# 09_UART_JTAG_GPIO.net
KiCad netlist of a schematic drawn in Altium Designer
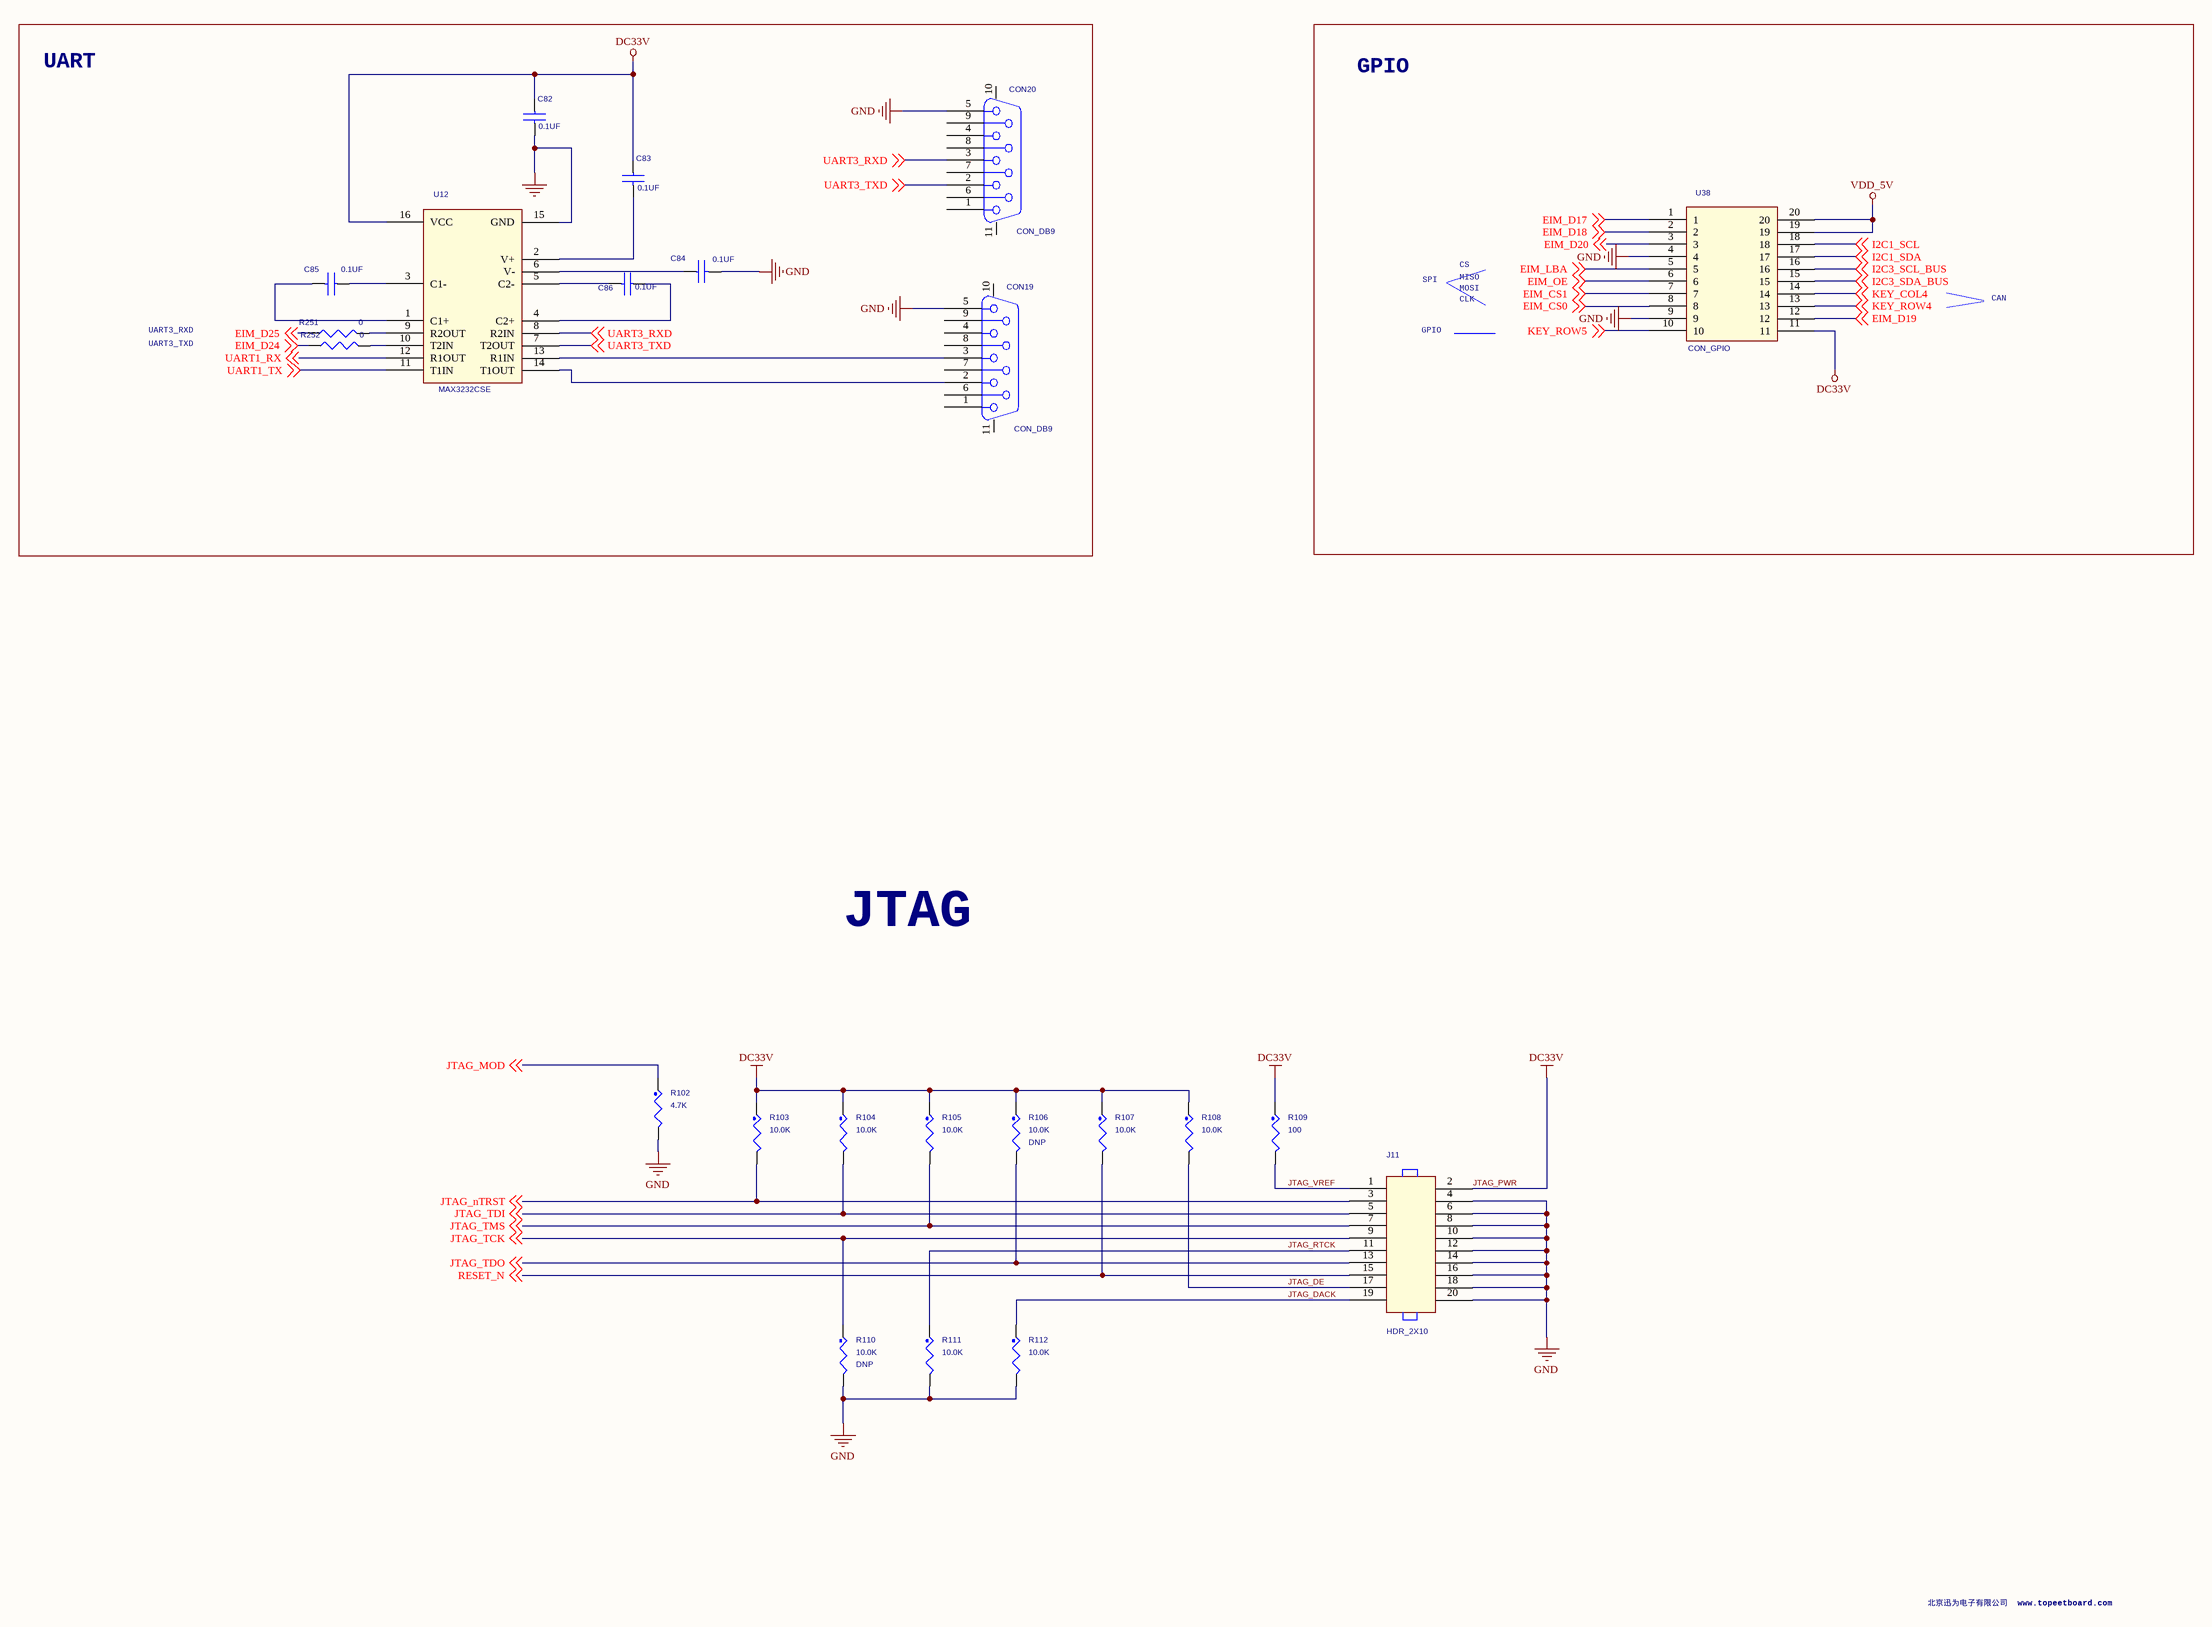
[diagram p0: 09 UART,JTAG,GPIO.SchDoc]

(export (version "E")
  (design (tool "Eeschema 10.0.6"))
  (components
    (comp (ref "C82") (value "0.1UF") (footprint "C0603") (libsource (lib "*") (part "C0603_0_Dup1")))
    (comp (ref "C83") (value "0.1UF") (footprint "C0603") (libsource (lib "*") (part "C0603_0_Dup1")))
    (comp (ref "C84") (value "0.1UF") (footprint "C0603") (libsource (lib "*") (part "C0603_0_Dup1")))
    (comp (ref "C85") (value "0.1UF") (footprint "C0603") (libsource (lib "*") (part "C0603_0_Dup1")))
    (comp (ref "C86") (value "0.1UF") (footprint "C0603") (libsource (lib "*") (part "C0603_0_Dup1")))
    (comp (ref "CON19") (value "CON_DB9") (footprint "DB9") (libsource (lib "*") (part "CON_DB9")))
    (comp (ref "CON20") (value "CON_DB9") (footprint "DB9") (libsource (lib "*") (part "CON_DB9")))
    (comp (ref "J11")
      (value "HDR_2X10")
      (description "HDR 2X10 TH SHRD 100MIL CTR 393H AU 120L")
      (libsource (lib "*") (part "HDR_2X10"))
    )
    (comp (ref "R102")
      (value "4.7K")
      (description "RES MF 4.70K 1/16W 1% 0402")
      (fields (field (name "TOLERANCE") "1%"))
      (libsource (lib "*") (part "RES_Dup1"))
    )
    (comp (ref "R103")
      (value "10.0K")
      (description "RES MF 10.0K 1/16W 1% AEC-Q200 0402")
      (fields (field (name "TOLERANCE") "1%"))
      (libsource (lib "*") (part "RES_Dup1"))
    )
    (comp (ref "R104")
      (value "10.0K")
      (description "RES MF 10.0K 1/16W 1% AEC-Q200 0402")
      (fields (field (name "TOLERANCE") "1%"))
      (libsource (lib "*") (part "RES_Dup1"))
    )
    (comp (ref "R105")
      (value "10.0K")
      (description "RES MF 10.0K 1/16W 1% AEC-Q200 0402")
      (fields (field (name "TOLERANCE") "1%"))
      (libsource (lib "*") (part "RES_Dup1"))
    )
    (comp (ref "R106")
      (value "10.0K")
      (description "RES MF 10.0K 1/16W 1% AEC-Q200 0402")
      (fields (field (name "TOLERANCE") "1%") (field (name "ASSY_OPT") "DNP"))
      (libsource (lib "*") (part "RES_Dup1"))
    )
    (comp (ref "R107")
      (value "10.0K")
      (description "RES MF 10.0K 1/16W 1% AEC-Q200 0402")
      (fields (field (name "TOLERANCE") "1%"))
      (libsource (lib "*") (part "RES_Dup1"))
    )
    (comp (ref "R108")
      (value "10.0K")
      (description "RES MF 10.0K 1/16W 1% AEC-Q200 0402")
      (fields (field (name "TOLERANCE") "1%"))
      (libsource (lib "*") (part "RES_Dup1"))
    )
    (comp (ref "R109")
      (value "100")
      (description "RES MF 100 OHM 1/16W 1% 0402")
      (fields (field (name "TOLERANCE") "1%"))
      (libsource (lib "*") (part "RES_Dup1"))
    )
    (comp (ref "R110")
      (value "10.0K")
      (description "RES MF 10.0K 1/16W 1% AEC-Q200 0402")
      (fields (field (name "TOLERANCE") "1%") (field (name "ASSY_OPT") "DNP"))
      (libsource (lib "*") (part "RES_Dup1"))
    )
    (comp (ref "R111")
      (value "10.0K")
      (description "RES MF 10.0K 1/16W 1% AEC-Q200 0402")
      (fields (field (name "TOLERANCE") "1%"))
      (libsource (lib "*") (part "RES_Dup1"))
    )
    (comp (ref "R112")
      (value "10.0K")
      (description "RES MF 10.0K 1/16W 1% AEC-Q200 0402")
      (fields (field (name "TOLERANCE") "1%"))
      (libsource (lib "*") (part "RES_Dup1"))
    )
    (comp (ref "R251") (value "0") (footprint "R1005") (libsource (lib "*") (part "R1005_0_Dup1")))
    (comp (ref "R252") (value "0") (footprint "R1005") (libsource (lib "*") (part "R1005_0_Dup1")))
    (comp (ref "U12") (value "MAX3232CSE") (footprint "16") (libsource (lib "*") (part "MAX3232EEAE")))
    (comp (ref "U38") (value "CON_GPIO") (libsource (lib "*") (part "CON20_1")))
  )
  (nets
    (net (code "1") (name "/JTAG_DACK") (class "Default")
      (node (ref "J11") (pin "19") (pinfunction "19_19") (pintype "passive"))
      (node (ref "R112") (pin "1") (pinfunction "1_1") (pintype "passive"))
    )
    (net (code "2") (name "/JTAG_DE") (class "Default")
      (node (ref "J11") (pin "17") (pinfunction "17_17") (pintype "passive"))
      (node (ref "R108") (pin "2") (pinfunction "2_2") (pintype "passive"))
    )
    (net (code "3") (name "/JTAG_RTCK") (class "Default")
      (node (ref "J11") (pin "11") (pinfunction "11_11") (pintype "passive"))
      (node (ref "R111") (pin "1") (pinfunction "1_1") (pintype "passive"))
    )
    (net (code "4") (name "/JTAG_VREF") (class "Default")
      (node (ref "J11") (pin "1") (pinfunction "1_1") (pintype "passive"))
      (node (ref "R109") (pin "2") (pinfunction "2_2") (pintype "passive"))
    )
    (net (code "5") (name "DC33V") (class "Default")
      (node (ref "C82") (pin "1") (pinfunction "1_1") (pintype "passive"))
      (node (ref "C83") (pin "1") (pinfunction "1_1") (pintype "passive"))
      (node (ref "J11") (pin "2") (pinfunction "2_2") (pintype "passive"))
      (node (ref "R103") (pin "1") (pinfunction "1_1") (pintype "passive"))
      (node (ref "R104") (pin "1") (pinfunction "1_1") (pintype "passive"))
      (node (ref "R105") (pin "1") (pinfunction "1_1") (pintype "passive"))
      (node (ref "R106") (pin "1") (pinfunction "1_1") (pintype "passive"))
      (node (ref "R107") (pin "1") (pinfunction "1_1") (pintype "passive"))
      (node (ref "R108") (pin "1") (pinfunction "1_1") (pintype "passive"))
      (node (ref "R109") (pin "1") (pinfunction "1_1") (pintype "passive"))
      (node (ref "U12") (pin "16") (pinfunction "VCC_16") (pintype "power_in"))
      (node (ref "U38") (pin "11") (pinfunction "11_11") (pintype "passive"))
    )
    (net (code "6") (name "EIM_CS0") (class "Default")
      (node (ref "U38") (pin "8") (pinfunction "8_8") (pintype "passive"))
    )
    (net (code "7") (name "EIM_CS1") (class "Default")
      (node (ref "U38") (pin "7") (pinfunction "7_7") (pintype "passive"))
    )
    (net (code "8") (name "EIM_D17") (class "Default")
      (node (ref "U38") (pin "1") (pinfunction "1_1") (pintype "passive"))
    )
    (net (code "9") (name "EIM_D18") (class "Default")
      (node (ref "U38") (pin "2") (pinfunction "2_2") (pintype "passive"))
    )
    (net (code "10") (name "EIM_D19") (class "Default")
      (node (ref "U38") (pin "12") (pinfunction "12_12") (pintype "passive"))
    )
    (net (code "11") (name "EIM_D20") (class "Default")
      (node (ref "U38") (pin "3") (pinfunction "3_3") (pintype "passive"))
    )
    (net (code "12") (name "EIM_D24") (class "Default")
      (node (ref "R252") (pin "1") (pinfunction "1_1") (pintype "passive"))
    )
    (net (code "13") (name "EIM_D25") (class "Default")
      (node (ref "R251") (pin "1") (pinfunction "1_1") (pintype "passive"))
    )
    (net (code "14") (name "EIM_LBA") (class "Default")
      (node (ref "U38") (pin "5") (pinfunction "5_5") (pintype "passive"))
    )
    (net (code "15") (name "EIM_OE") (class "Default")
      (node (ref "U38") (pin "6") (pinfunction "6_6") (pintype "passive"))
    )
    (net (code "16") (name "GND") (class "Default")
      (node (ref "C82") (pin "2") (pinfunction "2_2") (pintype "passive"))
      (node (ref "C84") (pin "2") (pinfunction "2_2") (pintype "passive"))
      (node (ref "CON19") (pin "5") (pinfunction "5_5") (pintype "passive"))
      (node (ref "CON20") (pin "5") (pinfunction "5_5") (pintype "passive"))
      (node (ref "J11") (pin "10") (pinfunction "10_10") (pintype "passive"))
      (node (ref "J11") (pin "12") (pinfunction "12_12") (pintype "passive"))
      (node (ref "J11") (pin "14") (pinfunction "14_14") (pintype "passive"))
      (node (ref "J11") (pin "16") (pinfunction "16_16") (pintype "passive"))
      (node (ref "J11") (pin "18") (pinfunction "18_18") (pintype "passive"))
      (node (ref "J11") (pin "20") (pinfunction "20_20") (pintype "passive"))
      (node (ref "J11") (pin "4") (pinfunction "4_4") (pintype "passive"))
      (node (ref "J11") (pin "6") (pinfunction "6_6") (pintype "passive"))
      (node (ref "J11") (pin "8") (pinfunction "8_8") (pintype "passive"))
      (node (ref "R102") (pin "2") (pinfunction "2_2") (pintype "passive"))
      (node (ref "R110") (pin "2") (pinfunction "2_2") (pintype "passive"))
      (node (ref "R111") (pin "2") (pinfunction "2_2") (pintype "passive"))
      (node (ref "R112") (pin "2") (pinfunction "2_2") (pintype "passive"))
      (node (ref "U12") (pin "15") (pinfunction "GND_15") (pintype "power_in"))
      (node (ref "U38") (pin "4") (pinfunction "4_4") (pintype "passive"))
      (node (ref "U38") (pin "9") (pinfunction "9_9") (pintype "passive"))
    )
    (net (code "17") (name "I2C1_SCL") (class "Default")
      (node (ref "U38") (pin "18") (pinfunction "18_18") (pintype "passive"))
    )
    (net (code "18") (name "I2C1_SDA") (class "Default")
      (node (ref "U38") (pin "17") (pinfunction "17_17") (pintype "passive"))
    )
    (net (code "19") (name "I2C3_SCL_BUS") (class "Default")
      (node (ref "U38") (pin "16") (pinfunction "16_16") (pintype "passive"))
    )
    (net (code "20") (name "I2C3_SDA_BUS") (class "Default")
      (node (ref "U38") (pin "15") (pinfunction "15_15") (pintype "passive"))
    )
    (net (code "21") (name "JTAG_MOD") (class "Default")
      (node (ref "R102") (pin "1") (pinfunction "1_1") (pintype "passive"))
    )
    (net (code "22") (name "JTAG_TCK") (class "Default")
      (node (ref "J11") (pin "9") (pinfunction "9_9") (pintype "passive"))
      (node (ref "R110") (pin "1") (pinfunction "1_1") (pintype "passive"))
    )
    (net (code "23") (name "JTAG_TDI") (class "Default")
      (node (ref "J11") (pin "5") (pinfunction "5_5") (pintype "passive"))
      (node (ref "R104") (pin "2") (pinfunction "2_2") (pintype "passive"))
    )
    (net (code "24") (name "JTAG_TDO") (class "Default")
      (node (ref "J11") (pin "13") (pinfunction "13_13") (pintype "passive"))
      (node (ref "R106") (pin "2") (pinfunction "2_2") (pintype "passive"))
    )
    (net (code "25") (name "JTAG_TMS") (class "Default")
      (node (ref "J11") (pin "7") (pinfunction "7_7") (pintype "passive"))
      (node (ref "R105") (pin "2") (pinfunction "2_2") (pintype "passive"))
    )
    (net (code "26") (name "JTAG_nTRST") (class "Default")
      (node (ref "J11") (pin "3") (pinfunction "3_3") (pintype "passive"))
      (node (ref "R103") (pin "2") (pinfunction "2_2") (pintype "passive"))
    )
    (net (code "27") (name "KEY_COL4") (class "Default")
      (node (ref "U38") (pin "14") (pinfunction "14_14") (pintype "passive"))
    )
    (net (code "28") (name "KEY_ROW4") (class "Default")
      (node (ref "U38") (pin "13") (pinfunction "13_13") (pintype "passive"))
    )
    (net (code "29") (name "KEY_ROW5") (class "Default")
      (node (ref "U38") (pin "10") (pinfunction "10_10") (pintype "passive"))
    )
    (net (code "30") (name "Net-(U12-C1+)") (class "Default")
      (node (ref "C85") (pin "2") (pinfunction "2_2") (pintype "passive"))
      (node (ref "U12") (pin "1") (pinfunction "C1+_1") (pintype "passive"))
    )
    (net (code "31") (name "Net-(U12-C1-)") (class "Default")
      (node (ref "C85") (pin "1") (pinfunction "1_1") (pintype "passive"))
      (node (ref "U12") (pin "3") (pinfunction "C1-_3") (pintype "passive"))
    )
    (net (code "32") (name "Net-(U12-C2+)") (class "Default")
      (node (ref "C86") (pin "1") (pinfunction "1_1") (pintype "passive"))
      (node (ref "U12") (pin "4") (pinfunction "C2+_4") (pintype "passive"))
    )
    (net (code "33") (name "Net-(U12-C2-)") (class "Default")
      (node (ref "C86") (pin "2") (pinfunction "2_2") (pintype "passive"))
      (node (ref "U12") (pin "5") (pinfunction "C2-_5") (pintype "passive"))
    )
    (net (code "34") (name "Net-(U12-R1IN)") (class "Default")
      (node (ref "CON19") (pin "3") (pinfunction "3_3") (pintype "passive"))
      (node (ref "U12") (pin "13") (pinfunction "R1IN_13") (pintype "passive"))
    )
    (net (code "35") (name "Net-(U12-R2OUT)") (class "Default")
      (node (ref "R251") (pin "2") (pinfunction "2_2") (pintype "passive"))
      (node (ref "U12") (pin "9") (pinfunction "R2OUT_9") (pintype "passive"))
    )
    (net (code "36") (name "Net-(U12-T1OUT)") (class "Default")
      (node (ref "CON19") (pin "2") (pinfunction "2_2") (pintype "passive"))
      (node (ref "U12") (pin "14") (pinfunction "T1OUT_14") (pintype "passive"))
    )
    (net (code "37") (name "Net-(U12-T2IN)") (class "Default")
      (node (ref "R252") (pin "2") (pinfunction "2_2") (pintype "passive"))
      (node (ref "U12") (pin "10") (pinfunction "T2IN_10") (pintype "passive"))
    )
    (net (code "38") (name "Net-(U12-V+)") (class "Default")
      (node (ref "C83") (pin "2") (pinfunction "2_2") (pintype "passive"))
      (node (ref "U12") (pin "2") (pinfunction "V+_2") (pintype "passive"))
    )
    (net (code "39") (name "Net-(U12-V-)") (class "Default")
      (node (ref "C84") (pin "1") (pinfunction "1_1") (pintype "passive"))
      (node (ref "U12") (pin "6") (pinfunction "V-_6") (pintype "passive"))
    )
    (net (code "40") (name "RESET_N") (class "Default")
      (node (ref "J11") (pin "15") (pinfunction "15_15") (pintype "passive"))
      (node (ref "R107") (pin "2") (pinfunction "2_2") (pintype "passive"))
    )
    (net (code "41") (name "UART1_RX") (class "Default")
      (node (ref "U12") (pin "12") (pinfunction "R1OUT_12") (pintype "passive"))
    )
    (net (code "42") (name "UART1_TX") (class "Default")
      (node (ref "U12") (pin "11") (pinfunction "T1IN_11") (pintype "passive"))
    )
    (net (code "43") (name "UART3_RXD") (class "Default")
      (node (ref "CON20") (pin "3") (pinfunction "3_3") (pintype "passive"))
      (node (ref "U12") (pin "8") (pinfunction "R2IN_8") (pintype "passive"))
    )
    (net (code "44") (name "UART3_TXD") (class "Default")
      (node (ref "CON20") (pin "2") (pinfunction "2_2") (pintype "passive"))
      (node (ref "U12") (pin "7") (pinfunction "T2OUT_7") (pintype "passive"))
    )
    (net (code "45") (name "VDD_5V") (class "Default")
      (node (ref "U38") (pin "19") (pinfunction "19_19") (pintype "passive"))
      (node (ref "U38") (pin "20") (pinfunction "20_20") (pintype "passive"))
    )
    (net (code "46") (name "unconnected-(CON19-Pad1)") (class "Default")
      (node (ref "CON19") (pin "1") (pinfunction "1_1") (pintype "passive"))
    )
    (net (code "47") (name "unconnected-(CON19-Pad4)") (class "Default")
      (node (ref "CON19") (pin "4") (pinfunction "4_4") (pintype "passive"))
    )
    (net (code "48") (name "unconnected-(CON19-Pad6)") (class "Default")
      (node (ref "CON19") (pin "6") (pinfunction "6_6") (pintype "passive"))
    )
    (net (code "49") (name "unconnected-(CON19-Pad7)") (class "Default")
      (node (ref "CON19") (pin "7") (pinfunction "7_7") (pintype "passive"))
    )
    (net (code "50") (name "unconnected-(CON19-Pad8)") (class "Default")
      (node (ref "CON19") (pin "8") (pinfunction "8_8") (pintype "passive"))
    )
    (net (code "51") (name "unconnected-(CON19-Pad9)") (class "Default")
      (node (ref "CON19") (pin "9") (pinfunction "9_9") (pintype "passive"))
    )
    (net (code "52") (name "unconnected-(CON19-Pad10)") (class "Default")
      (node (ref "CON19") (pin "10") (pinfunction "10_10") (pintype "passive"))
    )
    (net (code "53") (name "unconnected-(CON19-Pad11)") (class "Default")
      (node (ref "CON19") (pin "11") (pinfunction "11_11") (pintype "passive"))
    )
    (net (code "54") (name "unconnected-(CON20-Pad1)") (class "Default")
      (node (ref "CON20") (pin "1") (pinfunction "1_1") (pintype "passive"))
    )
    (net (code "55") (name "unconnected-(CON20-Pad4)") (class "Default")
      (node (ref "CON20") (pin "4") (pinfunction "4_4") (pintype "passive"))
    )
    (net (code "56") (name "unconnected-(CON20-Pad6)") (class "Default")
      (node (ref "CON20") (pin "6") (pinfunction "6_6") (pintype "passive"))
    )
    (net (code "57") (name "unconnected-(CON20-Pad7)") (class "Default")
      (node (ref "CON20") (pin "7") (pinfunction "7_7") (pintype "passive"))
    )
    (net (code "58") (name "unconnected-(CON20-Pad8)") (class "Default")
      (node (ref "CON20") (pin "8") (pinfunction "8_8") (pintype "passive"))
    )
    (net (code "59") (name "unconnected-(CON20-Pad9)") (class "Default")
      (node (ref "CON20") (pin "9") (pinfunction "9_9") (pintype "passive"))
    )
    (net (code "60") (name "unconnected-(CON20-Pad10)") (class "Default")
      (node (ref "CON20") (pin "10") (pinfunction "10_10") (pintype "passive"))
    )
    (net (code "61") (name "unconnected-(CON20-Pad11)") (class "Default")
      (node (ref "CON20") (pin "11") (pinfunction "11_11") (pintype "passive"))
    )
  )
)
